# Display.net
KiCad netlist of a schematic drawn in Altium Designer
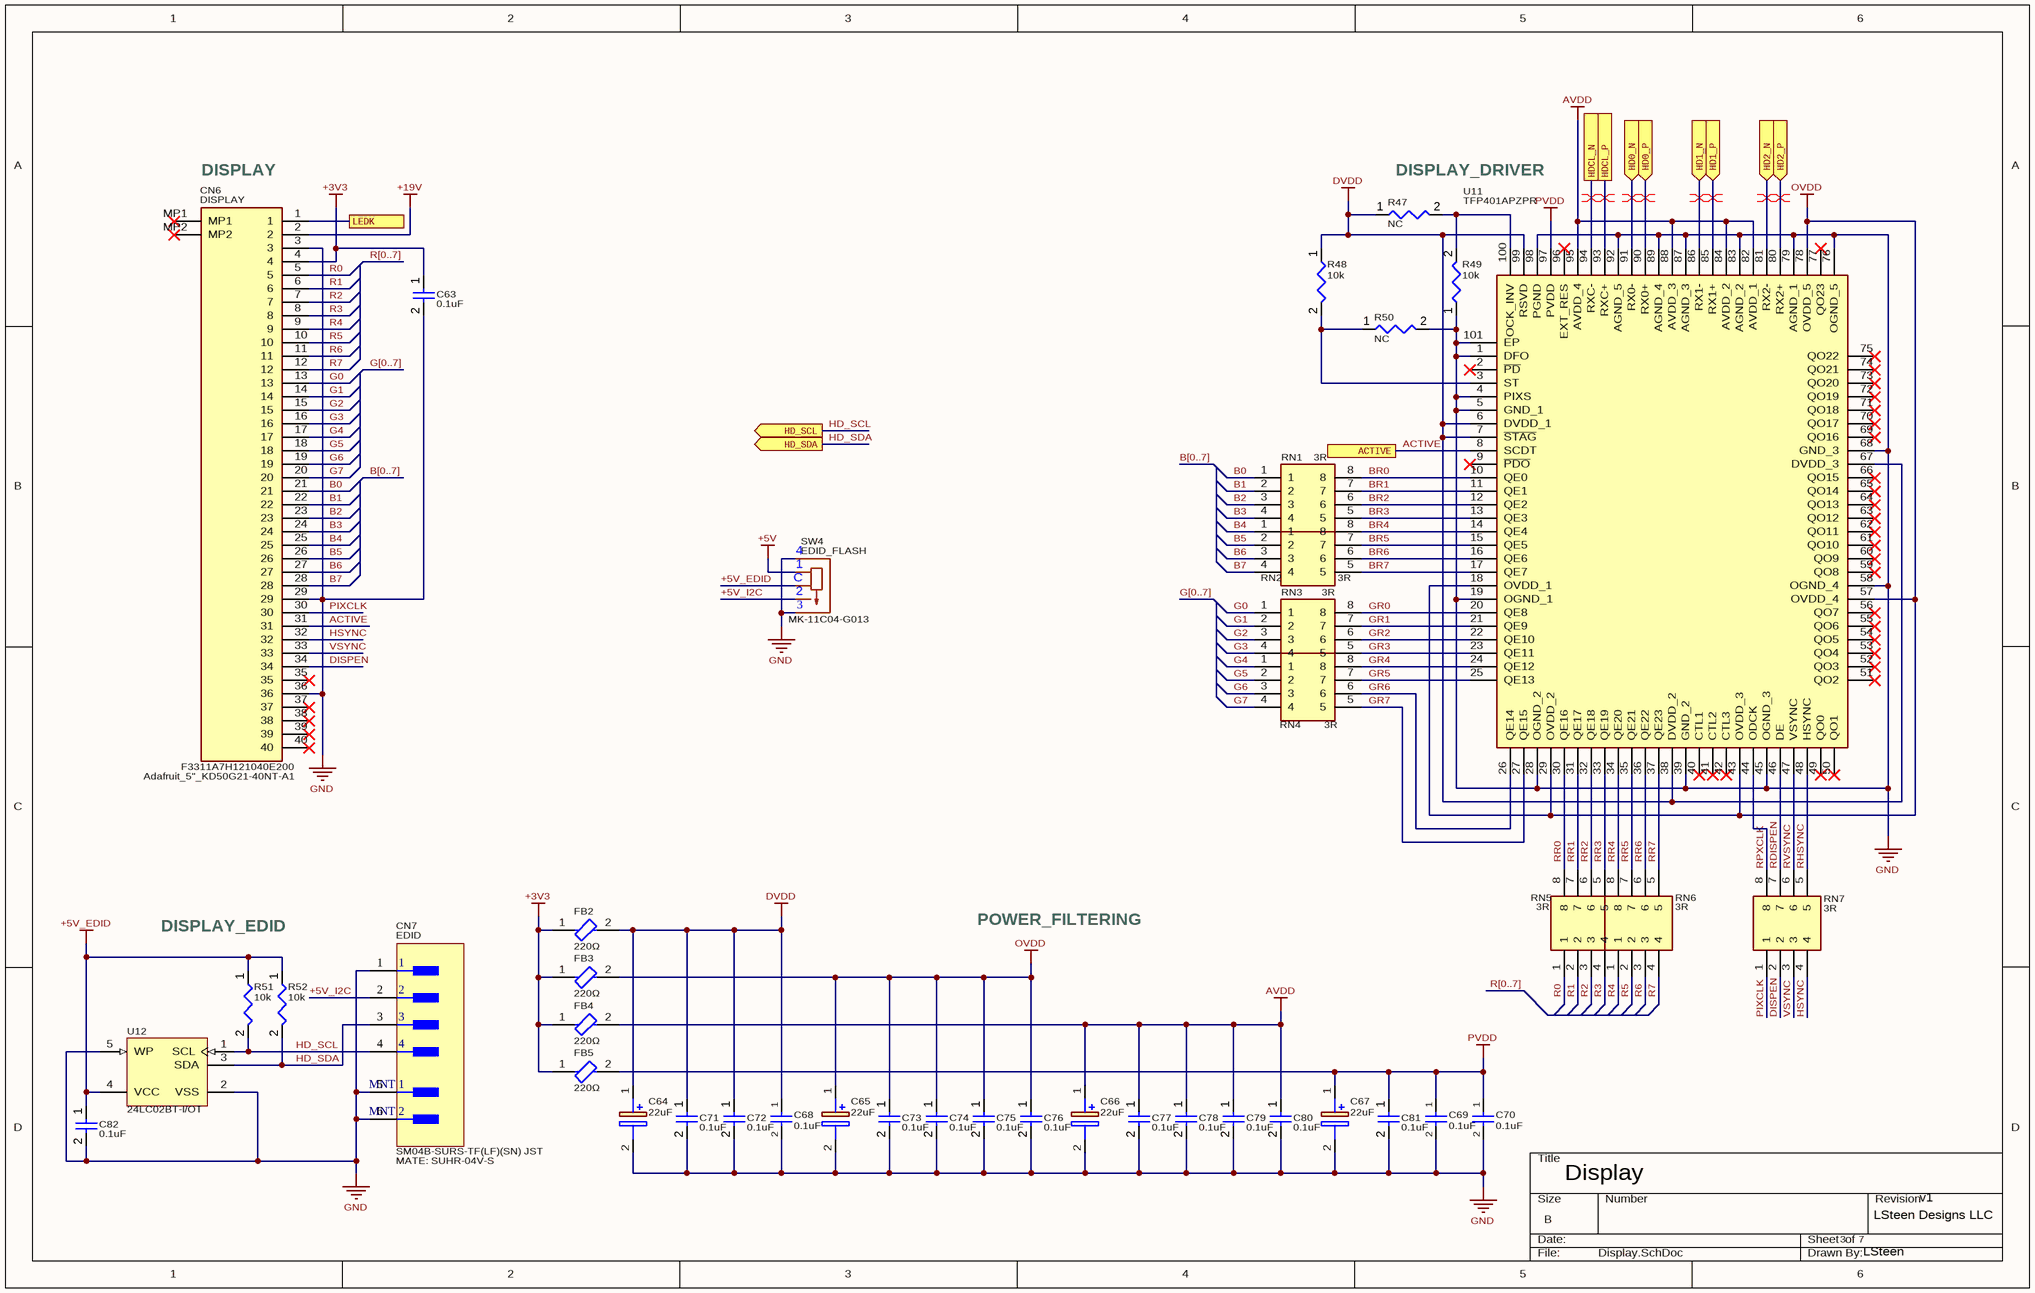
[diagram p0: Display.SchDoc]

(export (version "E")
  (design (tool "Eeschema 10.0.6"))
  (components
    (comp (ref "C63")
      (value "0.1uF")
      (footprint "CAPC1005X56X25LL10T15")
      (description "Chip Capacitor, 0.1 uF, +/- 5%, 16 V, 0402 (1005 Metric)")
      (fields (field (name "TOLERANCE") "5%"))
      (libsource (lib "Colorado Technical University") (part "CAP-NP-2"))
    )
    (comp (ref "C64")
      (value "22uF")
      (footprint "SamacSys:CAPPC2114X150N")
      (description "Capacitor Polarised")
      (fields
        (field (name "MANUFACTURER_PART_NUMBER") "TACR226K006XTA")
        (field (name "MOUSER PART NUMBER") "581-TACR226K006X")
      )
      (libsource (lib "SamacSys") (part "TACR226K006XTA"))
    )
    (comp (ref "C65")
      (value "22uF")
      (footprint "SamacSys:CAPPC2114X150N")
      (description "Capacitor Polarised")
      (fields
        (field (name "MANUFACTURER_PART_NUMBER") "TACR226K006XTA")
        (field (name "MOUSER PART NUMBER") "581-TACR226K006X")
      )
      (libsource (lib "SamacSys") (part "TACR226K006XTA"))
    )
    (comp (ref "C66")
      (value "22uF")
      (footprint "SamacSys:CAPPC2114X150N")
      (description "Capacitor Polarised")
      (fields
        (field (name "MANUFACTURER_PART_NUMBER") "TACR226K006XTA")
        (field (name "MOUSER PART NUMBER") "581-TACR226K006X")
      )
      (libsource (lib "SamacSys") (part "TACR226K006XTA"))
    )
    (comp (ref "C67")
      (value "22uF")
      (footprint "SamacSys:CAPPC2114X150N")
      (description "Capacitor Polarised")
      (fields
        (field (name "MANUFACTURER_PART_NUMBER") "TACR226K006XTA")
        (field (name "MOUSER PART NUMBER") "581-TACR226K006X")
      )
      (libsource (lib "SamacSys") (part "TACR226K006XTA"))
    )
    (comp (ref "C68")
      (value "0.1uF")
      (footprint "SamacSys:CAPC1005X55N")
      (description "C0402")
      (libsource (lib "SamacSys") (part "C0402"))
    )
    (comp (ref "C69")
      (value "0.1uF")
      (footprint "SamacSys:CAPC1005X55N")
      (description "C0402")
      (libsource (lib "SamacSys") (part "C0402"))
    )
    (comp (ref "C70")
      (value "0.1uF")
      (footprint "SamacSys:CAPC1005X55N")
      (description "C0402")
      (libsource (lib "SamacSys") (part "C0402"))
    )
    (comp (ref "C71")
      (value "0.1uF")
      (footprint "CAPC1005X56X25LL10T15")
      (description "Chip Capacitor, 0.1 uF, +/- 5%, 16 V, 0402 (1005 Metric)")
      (fields (field (name "TOLERANCE") "5%"))
      (libsource (lib "Colorado Technical University") (part "CAP-NP-2"))
    )
    (comp (ref "C72")
      (value "0.1uF")
      (footprint "CAPC1005X56X25LL10T15")
      (description "Chip Capacitor, 0.1 uF, +/- 5%, 16 V, 0402 (1005 Metric)")
      (fields (field (name "TOLERANCE") "5%"))
      (libsource (lib "Colorado Technical University") (part "CAP-NP-2"))
    )
    (comp (ref "C73")
      (value "0.1uF")
      (footprint "CAPC1005X56X25LL10T15")
      (description "Chip Capacitor, 0.1 uF, +/- 5%, 16 V, 0402 (1005 Metric)")
      (fields (field (name "TOLERANCE") "5%"))
      (libsource (lib "Colorado Technical University") (part "CAP-NP-2"))
    )
    (comp (ref "C74")
      (value "0.1uF")
      (footprint "CAPC1005X56X25LL10T15")
      (description "Chip Capacitor, 0.1 uF, +/- 5%, 16 V, 0402 (1005 Metric)")
      (fields (field (name "TOLERANCE") "5%"))
      (libsource (lib "Colorado Technical University") (part "CAP-NP-2"))
    )
    (comp (ref "C75")
      (value "0.1uF")
      (footprint "CAPC1005X56X25LL10T15")
      (description "Chip Capacitor, 0.1 uF, +/- 5%, 16 V, 0402 (1005 Metric)")
      (fields (field (name "TOLERANCE") "5%"))
      (libsource (lib "Colorado Technical University") (part "CAP-NP-2"))
    )
    (comp (ref "C76")
      (value "0.1uF")
      (footprint "CAPC1005X56X25LL10T15")
      (description "Chip Capacitor, 0.1 uF, +/- 5%, 16 V, 0402 (1005 Metric)")
      (fields (field (name "TOLERANCE") "5%"))
      (libsource (lib "Colorado Technical University") (part "CAP-NP-2"))
    )
    (comp (ref "C77")
      (value "0.1uF")
      (footprint "CAPC1005X56X25LL10T15")
      (description "Chip Capacitor, 0.1 uF, +/- 5%, 16 V, 0402 (1005 Metric)")
      (fields (field (name "TOLERANCE") "5%"))
      (libsource (lib "Colorado Technical University") (part "CAP-NP-2"))
    )
    (comp (ref "C78")
      (value "0.1uF")
      (footprint "CAPC1005X56X25LL10T15")
      (description "Chip Capacitor, 0.1 uF, +/- 5%, 16 V, 0402 (1005 Metric)")
      (fields (field (name "TOLERANCE") "5%"))
      (libsource (lib "Colorado Technical University") (part "CAP-NP-2"))
    )
    (comp (ref "C79")
      (value "0.1uF")
      (footprint "CAPC1005X56X25LL10T15")
      (description "Chip Capacitor, 0.1 uF, +/- 5%, 16 V, 0402 (1005 Metric)")
      (fields (field (name "TOLERANCE") "5%"))
      (libsource (lib "Colorado Technical University") (part "CAP-NP-2"))
    )
    (comp (ref "C80")
      (value "0.1uF")
      (footprint "CAPC1005X56X25LL10T15")
      (description "Chip Capacitor, 0.1 uF, +/- 5%, 16 V, 0402 (1005 Metric)")
      (fields (field (name "TOLERANCE") "5%"))
      (libsource (lib "Colorado Technical University") (part "CAP-NP-2"))
    )
    (comp (ref "C81")
      (value "0.1uF")
      (footprint "CAPC1005X56X25LL10T15")
      (description "Chip Capacitor, 0.1 uF, +/- 5%, 16 V, 0402 (1005 Metric)")
      (fields (field (name "TOLERANCE") "5%"))
      (libsource (lib "Colorado Technical University") (part "CAP-NP-2"))
    )
    (comp (ref "C82")
      (value "0.1uF")
      (footprint "CAPC1005X56X25LL10T15")
      (description "Chip Capacitor, 0.1 uF, +/- 5%, 16 V, 0402 (1005 Metric)")
      (fields (field (name "TOLERANCE") "5%"))
      (libsource (lib "Colorado Technical University") (part "CAP-NP-2"))
    )
    (comp (ref "CN6")
      (value "DISPLAY")
      (footprint "SamacSys:F3311A7H121040E200")
      (description "Connector")
      (fields (field (name "MANUFACTURER_PART_NUMBER") "F3311A7H121040E200"))
      (libsource (lib "*") (part "F3311A7H121040E200"))
    )
    (comp (ref "CN7")
      (value "EDID")
      (footprint "FP-SM04B-SURS-TF_LF_SN-MFG")
      (description "CONN HEADER SMD R/A 4POS 0.8MM")
      (libsource (lib "Altium Content Vault") (part "3b6f738a5616415d78381ad43816e4a"))
    )
    (comp (ref "FB2")
      (value "220Ω")
      (footprint "FP-BLM18-0_15-t0_5-IPC_B")
      (description "Chip Ferrite Bead, 0603, 220Ω @ 100MHz, 25%, 0.04Ω, 2.5A")
      (libsource (lib "Altium Content Vault") (part "5f30dd21d616792df468990f7003faa"))
    )
    (comp (ref "FB3")
      (value "220Ω")
      (footprint "FP-BLM18-0_15-t0_5-IPC_B")
      (description "Chip Ferrite Bead, 0603, 220Ω @ 100MHz, 25%, 0.04Ω, 2.5A")
      (libsource (lib "Altium Content Vault") (part "5f30dd21d616792df468990f7003faa"))
    )
    (comp (ref "FB4")
      (value "220Ω")
      (footprint "FP-BLM18-0_15-t0_5-IPC_B")
      (description "Chip Ferrite Bead, 0603, 220Ω @ 100MHz, 25%, 0.04Ω, 2.5A")
      (libsource (lib "Altium Content Vault") (part "5f30dd21d616792df468990f7003faa"))
    )
    (comp (ref "FB5")
      (value "220Ω")
      (footprint "FP-BLM18-0_15-t0_5-IPC_B")
      (description "Chip Ferrite Bead, 0603, 220Ω @ 100MHz, 25%, 0.04Ω, 2.5A")
      (libsource (lib "Altium Content Vault") (part "5f30dd21d616792df468990f7003faa"))
    )
    (comp (ref "R47")
      (value "NC")
      (footprint "RESC0402(1005)_L")
      (description "Chip Resistor, 0 Ohms, +/-5 %, 63 mW, -55 to 155 degC, 0402")
      (fields (field (name "TOLERANCE") "5%") (field (name "POWER") "63mW"))
      (libsource (lib "Colorado Technical University") (part "RES-2"))
    )
    (comp (ref "R48")
      (value "10k")
      (footprint "RESC0402(1005)_L")
      (description "Chip Resistor, 10 kOhms, +/-5 %, 63 mW, -55 to 155 degC, 0402")
      (fields (field (name "TOLERANCE") "5%") (field (name "POWER") "63mW"))
      (libsource (lib "Colorado Technical University") (part "RES-2"))
    )
    (comp (ref "R49")
      (value "10k")
      (footprint "RESC0402(1005)_L")
      (description "Chip Resistor, 10 kOhms, +/-5 %, 63 mW, -55 to 155 degC, 0402")
      (fields (field (name "TOLERANCE") "5%") (field (name "POWER") "63mW"))
      (libsource (lib "Colorado Technical University") (part "RES-2"))
    )
    (comp (ref "R50")
      (value "NC")
      (footprint "RESC0402(1005)_L")
      (description "Chip Resistor, 0 Ohms, +/-5 %, 63 mW, -55 to 155 degC, 0402")
      (fields (field (name "TOLERANCE") "5%") (field (name "POWER") "63mW"))
      (libsource (lib "Colorado Technical University") (part "RES-2"))
    )
    (comp (ref "R51")
      (value "10k")
      (footprint "RESC0402(1005)_L")
      (description "Chip Resistor, 10 kOhms, +/-5 %, 63 mW, -55 to 155 degC, 0402")
      (fields (field (name "TOLERANCE") "5%") (field (name "POWER") "63mW"))
      (libsource (lib "Colorado Technical University") (part "RES-2"))
    )
    (comp (ref "R52")
      (value "10k")
      (footprint "RESC0402(1005)_L")
      (description "Chip Resistor, 10 kOhms, +/-5 %, 63 mW, -55 to 155 degC, 0402")
      (fields (field (name "TOLERANCE") "5%") (field (name "POWER") "63mW"))
      (libsource (lib "Colorado Technical University") (part "RES-2"))
    )
    (comp (ref "RN1")
      (value "3R")
      (footprint "SamacSys:YC124JR0733RL")
      (description "Resistor Network")
      (fields
        (field (name "MANUFACTURER_PART_NUMBER") "YC124-JR-0733RL")
        (field (name "MOUSER PART NUMBER") "603-YC124-JR-0733RL")
      )
      (libsource (lib "") (part "YC124-JR-073RL_1"))
    )
    (comp (ref "RN2")
      (value "3R")
      (footprint "SamacSys:YC124JR0733RL")
      (description "Resistor Network")
      (fields
        (field (name "MANUFACTURER_PART_NUMBER") "YC124-JR-0733RL")
        (field (name "MOUSER PART NUMBER") "603-YC124-JR-0733RL")
      )
      (libsource (lib "") (part "YC124-JR-073RL_1"))
    )
    (comp (ref "RN3")
      (value "3R")
      (footprint "SamacSys:YC124JR0733RL")
      (description "Resistor Network")
      (fields
        (field (name "MANUFACTURER_PART_NUMBER") "YC124-JR-0733RL")
        (field (name "MOUSER PART NUMBER") "603-YC124-JR-0733RL")
      )
      (libsource (lib "") (part "YC124-JR-073RL_1"))
    )
    (comp (ref "RN4")
      (value "3R")
      (footprint "SamacSys:YC124JR0733RL")
      (description "Resistor Network")
      (fields
        (field (name "MANUFACTURER_PART_NUMBER") "YC124-JR-0733RL")
        (field (name "MOUSER PART NUMBER") "603-YC124-JR-0733RL")
      )
      (libsource (lib "") (part "YC124-JR-073RL_1"))
    )
    (comp (ref "RN5")
      (value "3R")
      (footprint "SamacSys:YC124JR0733RL")
      (description "Resistor Network")
      (fields
        (field (name "MANUFACTURER_PART_NUMBER") "YC124-JR-0733RL")
        (field (name "MOUSER PART NUMBER") "603-YC124-JR-0733RL")
      )
      (libsource (lib "SamacSys") (part "YC124-JR-073RL"))
    )
    (comp (ref "RN6")
      (value "3R")
      (footprint "SamacSys:YC124JR0733RL")
      (description "Resistor Network")
      (fields
        (field (name "MANUFACTURER_PART_NUMBER") "YC124-JR-0733RL")
        (field (name "MOUSER PART NUMBER") "603-YC124-JR-0733RL")
      )
      (libsource (lib "SamacSys") (part "YC124-JR-073RL"))
    )
    (comp (ref "RN7")
      (value "3R")
      (footprint "SamacSys:YC124JR0733RL")
      (description "Resistor Network")
      (fields
        (field (name "MANUFACTURER_PART_NUMBER") "YC124-JR-0733RL")
        (field (name "MOUSER PART NUMBER") "603-YC124-JR-0733RL")
      )
      (libsource (lib "SamacSys") (part "YC124-JR-073RL"))
    )
    (comp (ref "SW4")
      (value "EDID_FLASH")
      (footprint "SW-SMD_MK-11C04-G013")
      (description "SPDT 1A 6V Slide Switch")
      (libsource (lib "Schlib1") (part "MK-11C04-G013"))
    )
    (comp (ref "U11")
      (value "TFP401APZPR")
      (footprint "SamacSys:QFP50P1600X1600X120-100N")
      (description "Integrated Circuit")
      (fields (field (name "MOUSER PART NUMBER") "595-TFP401APZPR"))
      (libsource (lib "SamacSys") (part "TFP401APZPR"))
    )
    (comp (ref "U12")
      (value "24LC02BT-I/OT")
      (footprint "SOT-23-OT5_L")
      (description "2Kbit, 400kHz, 2.5V, I2C Serial EEPROM, 5-Pin SOT-23, Industrial Temperature, Tape and Reel")
      (libsource (lib "Altium Content Vault") (part "MEM-SEEPROM-24AA16-OT-5"))
    )
  )
  (nets
    (net (code "1") (name "+3V3") (class "Default")
      (node (ref "C63") (pin "1") (pinfunction "1_1") (pintype "passive"))
      (node (ref "CN6") (pin "4") (pinfunction "4_4") (pintype "passive"))
      (node (ref "FB2") (pin "1") (pinfunction "1_1") (pintype "passive"))
      (node (ref "FB3") (pin "1") (pinfunction "1_1") (pintype "passive"))
      (node (ref "FB4") (pin "1") (pinfunction "1_1") (pintype "passive"))
      (node (ref "FB5") (pin "1") (pinfunction "1_1") (pintype "passive"))
    )
    (net (code "2") (name "+5V") (class "Default")
      (node (ref "SW4") (pin "1") (pinfunction "1_1") (pintype "power_in"))
    )
    (net (code "3") (name "+5V_EDID") (class "Default")
      (node (ref "C82") (pin "1") (pinfunction "1_1") (pintype "passive"))
      (node (ref "R51") (pin "1") (pinfunction "1_1") (pintype "passive"))
      (node (ref "R52") (pin "1") (pinfunction "1_1") (pintype "passive"))
      (node (ref "SW4") (pin "C") (pinfunction "C_C") (pintype "power_in"))
      (node (ref "U12") (pin "4") (pinfunction "VCC_4") (pintype "power_in"))
    )
    (net (code "4") (name "+19V") (class "Default")
      (node (ref "CN6") (pin "2") (pinfunction "2_2") (pintype "passive"))
    )
    (net (code "5") (name "/+5V_I2C") (class "Default")
      (node (ref "CN7") (pin "2") (pinfunction "2_2") (pintype "passive"))
      (node (ref "SW4") (pin "2") (pinfunction "2_2") (pintype "passive"))
    )
    (net (code "6") (name "/ACTIVE") (class "Default")
      (node (ref "CN6") (pin "31") (pinfunction "31_31") (pintype "passive"))
      (node (ref "U11") (pin "8") (pinfunction "SCDT_8") (pintype "passive"))
    )
    (net (code "7") (name "/B0") (class "Default")
      (node (ref "CN6") (pin "21") (pinfunction "21_21") (pintype "passive"))
      (node (ref "RN1") (pin "1") (pinfunction "1_1") (pintype "passive"))
    )
    (net (code "8") (name "/B1") (class "Default")
      (node (ref "CN6") (pin "22") (pinfunction "22_22") (pintype "passive"))
      (node (ref "RN1") (pin "2") (pinfunction "2_2") (pintype "passive"))
    )
    (net (code "9") (name "/B2") (class "Default")
      (node (ref "CN6") (pin "23") (pinfunction "23_23") (pintype "passive"))
      (node (ref "RN1") (pin "3") (pinfunction "3_3") (pintype "passive"))
    )
    (net (code "10") (name "/B3") (class "Default")
      (node (ref "CN6") (pin "24") (pinfunction "24_24") (pintype "passive"))
      (node (ref "RN1") (pin "4") (pinfunction "4_4") (pintype "passive"))
    )
    (net (code "11") (name "/B4") (class "Default")
      (node (ref "CN6") (pin "25") (pinfunction "25_25") (pintype "passive"))
      (node (ref "RN2") (pin "1") (pinfunction "1_1") (pintype "passive"))
    )
    (net (code "12") (name "/B5") (class "Default")
      (node (ref "CN6") (pin "26") (pinfunction "26_26") (pintype "passive"))
      (node (ref "RN2") (pin "2") (pinfunction "2_2") (pintype "passive"))
    )
    (net (code "13") (name "/B6") (class "Default")
      (node (ref "CN6") (pin "27") (pinfunction "27_27") (pintype "passive"))
      (node (ref "RN2") (pin "3") (pinfunction "3_3") (pintype "passive"))
    )
    (net (code "14") (name "/B7") (class "Default")
      (node (ref "CN6") (pin "28") (pinfunction "28_28") (pintype "passive"))
      (node (ref "RN2") (pin "4") (pinfunction "4_4") (pintype "passive"))
    )
    (net (code "15") (name "/BR0") (class "Default")
      (node (ref "RN1") (pin "8") (pinfunction "8_8") (pintype "passive"))
      (node (ref "U11") (pin "10") (pinfunction "QE0_10") (pintype "passive"))
    )
    (net (code "16") (name "/BR1") (class "Default")
      (node (ref "RN1") (pin "7") (pinfunction "7_7") (pintype "passive"))
      (node (ref "U11") (pin "11") (pinfunction "QE1_11") (pintype "passive"))
    )
    (net (code "17") (name "/BR2") (class "Default")
      (node (ref "RN1") (pin "6") (pinfunction "6_6") (pintype "passive"))
      (node (ref "U11") (pin "12") (pinfunction "QE2_12") (pintype "passive"))
    )
    (net (code "18") (name "/BR3") (class "Default")
      (node (ref "RN1") (pin "5") (pinfunction "5_5") (pintype "passive"))
      (node (ref "U11") (pin "13") (pinfunction "QE3_13") (pintype "passive"))
    )
    (net (code "19") (name "/BR4") (class "Default")
      (node (ref "RN2") (pin "8") (pinfunction "8_8") (pintype "passive"))
      (node (ref "U11") (pin "14") (pinfunction "QE4_14") (pintype "passive"))
    )
    (net (code "20") (name "/BR5") (class "Default")
      (node (ref "RN2") (pin "7") (pinfunction "7_7") (pintype "passive"))
      (node (ref "U11") (pin "15") (pinfunction "QE5_15") (pintype "passive"))
    )
    (net (code "21") (name "/BR6") (class "Default")
      (node (ref "RN2") (pin "6") (pinfunction "6_6") (pintype "passive"))
      (node (ref "U11") (pin "16") (pinfunction "QE6_16") (pintype "passive"))
    )
    (net (code "22") (name "/BR7") (class "Default")
      (node (ref "RN2") (pin "5") (pinfunction "5_5") (pintype "passive"))
      (node (ref "U11") (pin "17") (pinfunction "QE7_17") (pintype "passive"))
    )
    (net (code "24") (name "/DISPEN") (class "Default")
      (node (ref "CN6") (pin "34") (pinfunction "34_34") (pintype "passive"))
      (node (ref "RN7") (pin "2") (pinfunction "2_2") (pintype "passive"))
    )
    (net (code "25") (name "/G0") (class "Default")
      (node (ref "CN6") (pin "13") (pinfunction "13_13") (pintype "passive"))
      (node (ref "RN3") (pin "1") (pinfunction "1_1") (pintype "passive"))
    )
    (net (code "26") (name "/G1") (class "Default")
      (node (ref "CN6") (pin "14") (pinfunction "14_14") (pintype "passive"))
      (node (ref "RN3") (pin "2") (pinfunction "2_2") (pintype "passive"))
    )
    (net (code "27") (name "/G2") (class "Default")
      (node (ref "CN6") (pin "15") (pinfunction "15_15") (pintype "passive"))
      (node (ref "RN3") (pin "3") (pinfunction "3_3") (pintype "passive"))
    )
    (net (code "28") (name "/G3") (class "Default")
      (node (ref "CN6") (pin "16") (pinfunction "16_16") (pintype "passive"))
      (node (ref "RN3") (pin "4") (pinfunction "4_4") (pintype "passive"))
    )
    (net (code "29") (name "/G4") (class "Default")
      (node (ref "CN6") (pin "17") (pinfunction "17_17") (pintype "passive"))
      (node (ref "RN4") (pin "1") (pinfunction "1_1") (pintype "passive"))
    )
    (net (code "30") (name "/G5") (class "Default")
      (node (ref "CN6") (pin "18") (pinfunction "18_18") (pintype "passive"))
      (node (ref "RN4") (pin "2") (pinfunction "2_2") (pintype "passive"))
    )
    (net (code "31") (name "/G6") (class "Default")
      (node (ref "CN6") (pin "19") (pinfunction "19_19") (pintype "passive"))
      (node (ref "RN4") (pin "3") (pinfunction "3_3") (pintype "passive"))
    )
    (net (code "32") (name "/G7") (class "Default")
      (node (ref "CN6") (pin "20") (pinfunction "20_20") (pintype "passive"))
      (node (ref "RN4") (pin "4") (pinfunction "4_4") (pintype "passive"))
    )
    (net (code "33") (name "/GR0") (class "Default")
      (node (ref "RN3") (pin "8") (pinfunction "8_8") (pintype "passive"))
      (node (ref "U11") (pin "20") (pinfunction "QE8_20") (pintype "passive"))
    )
    (net (code "34") (name "/GR1") (class "Default")
      (node (ref "RN3") (pin "7") (pinfunction "7_7") (pintype "passive"))
      (node (ref "U11") (pin "21") (pinfunction "QE9_21") (pintype "passive"))
    )
    (net (code "35") (name "/GR2") (class "Default")
      (node (ref "RN3") (pin "6") (pinfunction "6_6") (pintype "passive"))
      (node (ref "U11") (pin "22") (pinfunction "QE10_22") (pintype "passive"))
    )
    (net (code "36") (name "/GR3") (class "Default")
      (node (ref "RN3") (pin "5") (pinfunction "5_5") (pintype "passive"))
      (node (ref "U11") (pin "23") (pinfunction "QE11_23") (pintype "passive"))
    )
    (net (code "37") (name "/GR4") (class "Default")
      (node (ref "RN4") (pin "8") (pinfunction "8_8") (pintype "passive"))
      (node (ref "U11") (pin "24") (pinfunction "QE12_24") (pintype "passive"))
    )
    (net (code "38") (name "/GR5") (class "Default")
      (node (ref "RN4") (pin "7") (pinfunction "7_7") (pintype "passive"))
      (node (ref "U11") (pin "25") (pinfunction "QE13_25") (pintype "passive"))
    )
    (net (code "39") (name "/GR6") (class "Default")
      (node (ref "RN4") (pin "6") (pinfunction "6_6") (pintype "passive"))
      (node (ref "U11") (pin "26") (pinfunction "QE14_26") (pintype "passive"))
    )
    (net (code "40") (name "/GR7") (class "Default")
      (node (ref "RN4") (pin "5") (pinfunction "5_5") (pintype "passive"))
      (node (ref "U11") (pin "27") (pinfunction "QE15_27") (pintype "passive"))
    )
    (net (code "42") (name "/HD0_N") (class "Default")
      (node (ref "U11") (pin "91") (pinfunction "RX0-_91") (pintype "passive"))
    )
    (net (code "43") (name "/HD0_P") (class "Default")
      (node (ref "U11") (pin "90") (pinfunction "RX0+_90") (pintype "passive"))
    )
    (net (code "44") (name "/HD1_N") (class "Default")
      (node (ref "U11") (pin "86") (pinfunction "RX1-_86") (pintype "passive"))
    )
    (net (code "45") (name "/HD1_P") (class "Default")
      (node (ref "U11") (pin "85") (pinfunction "RX1+_85") (pintype "passive"))
    )
    (net (code "46") (name "/HD2_N") (class "Default")
      (node (ref "U11") (pin "81") (pinfunction "RX2-_81") (pintype "passive"))
    )
    (net (code "47") (name "/HD2_P") (class "Default")
      (node (ref "U11") (pin "80") (pinfunction "RX2+_80") (pintype "passive"))
    )
    (net (code "48") (name "/HDCL_N") (class "Default")
      (node (ref "U11") (pin "94") (pinfunction "RXC-_94") (pintype "passive"))
    )
    (net (code "49") (name "/HDCL_P") (class "Default")
      (node (ref "U11") (pin "93") (pinfunction "RXC+_93") (pintype "passive"))
    )
    (net (code "50") (name "/HD_SCL") (class "Default")
      (node (ref "CN7") (pin "4") (pinfunction "4_4") (pintype "passive"))
      (node (ref "R51") (pin "2") (pinfunction "2_2") (pintype "passive"))
      (node (ref "U12") (pin "1") (pinfunction "SCL_1") (pintype "input"))
    )
    (net (code "51") (name "/HD_SDA") (class "Default")
      (node (ref "CN7") (pin "3") (pinfunction "3_3") (pintype "passive"))
      (node (ref "R52") (pin "2") (pinfunction "2_2") (pintype "passive"))
      (node (ref "U12") (pin "3") (pinfunction "SDA_3") (pintype "passive"))
    )
    (net (code "52") (name "/HSYNC") (class "Default")
      (node (ref "CN6") (pin "32") (pinfunction "32_32") (pintype "passive"))
      (node (ref "RN7") (pin "4") (pinfunction "4_4") (pintype "passive"))
    )
    (net (code "53") (name "/LEDK") (class "Default")
      (node (ref "CN6") (pin "1") (pinfunction "1_1") (pintype "passive"))
    )
    (net (code "54") (name "/PIXCLK") (class "Default")
      (node (ref "CN6") (pin "30") (pinfunction "30_30") (pintype "passive"))
      (node (ref "RN7") (pin "1") (pinfunction "1_1") (pintype "passive"))
    )
    (net (code "55") (name "/R0") (class "Default")
      (node (ref "CN6") (pin "5") (pinfunction "5_5") (pintype "passive"))
      (node (ref "RN5") (pin "1") (pinfunction "1_1") (pintype "passive"))
    )
    (net (code "56") (name "/R1") (class "Default")
      (node (ref "CN6") (pin "6") (pinfunction "6_6") (pintype "passive"))
      (node (ref "RN5") (pin "2") (pinfunction "2_2") (pintype "passive"))
    )
    (net (code "57") (name "/R2") (class "Default")
      (node (ref "CN6") (pin "7") (pinfunction "7_7") (pintype "passive"))
      (node (ref "RN5") (pin "3") (pinfunction "3_3") (pintype "passive"))
    )
    (net (code "58") (name "/R3") (class "Default")
      (node (ref "CN6") (pin "8") (pinfunction "8_8") (pintype "passive"))
      (node (ref "RN5") (pin "4") (pinfunction "4_4") (pintype "passive"))
    )
    (net (code "59") (name "/R4") (class "Default")
      (node (ref "CN6") (pin "9") (pinfunction "9_9") (pintype "passive"))
      (node (ref "RN6") (pin "1") (pinfunction "1_1") (pintype "passive"))
    )
    (net (code "60") (name "/R5") (class "Default")
      (node (ref "CN6") (pin "10") (pinfunction "10_10") (pintype "passive"))
      (node (ref "RN6") (pin "2") (pinfunction "2_2") (pintype "passive"))
    )
    (net (code "61") (name "/R6") (class "Default")
      (node (ref "CN6") (pin "11") (pinfunction "11_11") (pintype "passive"))
      (node (ref "RN6") (pin "3") (pinfunction "3_3") (pintype "passive"))
    )
    (net (code "62") (name "/R7") (class "Default")
      (node (ref "CN6") (pin "12") (pinfunction "12_12") (pintype "passive"))
      (node (ref "RN6") (pin "4") (pinfunction "4_4") (pintype "passive"))
    )
    (net (code "63") (name "/RDISPEN") (class "Default")
      (node (ref "RN7") (pin "7") (pinfunction "7_7") (pintype "passive"))
      (node (ref "U11") (pin "46") (pinfunction "DE_46") (pintype "passive"))
    )
    (net (code "64") (name "/RHSYNC") (class "Default")
      (node (ref "RN7") (pin "5") (pinfunction "5_5") (pintype "passive"))
      (node (ref "U11") (pin "48") (pinfunction "HSYNC_48") (pintype "passive"))
    )
    (net (code "65") (name "/RPXCLK") (class "Default")
      (node (ref "RN7") (pin "8") (pinfunction "8_8") (pintype "passive"))
      (node (ref "U11") (pin "44") (pinfunction "ODCK_44") (pintype "passive"))
    )
    (net (code "66") (name "/RR0") (class "Default")
      (node (ref "RN5") (pin "8") (pinfunction "8_8") (pintype "passive"))
      (node (ref "U11") (pin "30") (pinfunction "QE16_30") (pintype "passive"))
    )
    (net (code "67") (name "/RR1") (class "Default")
      (node (ref "RN5") (pin "7") (pinfunction "7_7") (pintype "passive"))
      (node (ref "U11") (pin "31") (pinfunction "QE17_31") (pintype "passive"))
    )
    (net (code "68") (name "/RR2") (class "Default")
      (node (ref "RN5") (pin "6") (pinfunction "6_6") (pintype "passive"))
      (node (ref "U11") (pin "32") (pinfunction "QE18_32") (pintype "passive"))
    )
    (net (code "69") (name "/RR3") (class "Default")
      (node (ref "RN5") (pin "5") (pinfunction "5_5") (pintype "passive"))
      (node (ref "U11") (pin "33") (pinfunction "QE19_33") (pintype "passive"))
    )
    (net (code "70") (name "/RR4") (class "Default")
      (node (ref "RN6") (pin "8") (pinfunction "8_8") (pintype "passive"))
      (node (ref "U11") (pin "34") (pinfunction "QE20_34") (pintype "passive"))
    )
    (net (code "71") (name "/RR5") (class "Default")
      (node (ref "RN6") (pin "7") (pinfunction "7_7") (pintype "passive"))
      (node (ref "U11") (pin "35") (pinfunction "QE21_35") (pintype "passive"))
    )
    (net (code "72") (name "/RR6") (class "Default")
      (node (ref "RN6") (pin "6") (pinfunction "6_6") (pintype "passive"))
      (node (ref "U11") (pin "36") (pinfunction "QE22_36") (pintype "passive"))
    )
    (net (code "73") (name "/RR7") (class "Default")
      (node (ref "RN6") (pin "5") (pinfunction "5_5") (pintype "passive"))
      (node (ref "U11") (pin "37") (pinfunction "QE23_37") (pintype "passive"))
    )
    (net (code "74") (name "/RVSYNC") (class "Default")
      (node (ref "RN7") (pin "6") (pinfunction "6_6") (pintype "passive"))
      (node (ref "U11") (pin "47") (pinfunction "VSYNC_47") (pintype "passive"))
    )
    (net (code "76") (name "/VSYNC") (class "Default")
      (node (ref "CN6") (pin "33") (pinfunction "33_33") (pintype "passive"))
      (node (ref "RN7") (pin "3") (pinfunction "3_3") (pintype "passive"))
    )
    (net (code "77") (name "AVDD") (class "Default")
      (node (ref "C66") (pin "1") (pinfunction "+_1") (pintype "passive"))
      (node (ref "C77") (pin "1") (pinfunction "1_1") (pintype "passive"))
      (node (ref "C78") (pin "1") (pinfunction "1_1") (pintype "passive"))
      (node (ref "C79") (pin "1") (pinfunction "1_1") (pintype "passive"))
      (node (ref "C80") (pin "1") (pinfunction "1_1") (pintype "passive"))
      (node (ref "FB4") (pin "2") (pinfunction "2_2") (pintype "passive"))
      (node (ref "U11") (pin "82") (pinfunction "AVDD_1_82") (pintype "passive"))
      (node (ref "U11") (pin "84") (pinfunction "AVDD_2_84") (pintype "passive"))
      (node (ref "U11") (pin "88") (pinfunction "AVDD_3_88") (pintype "passive"))
      (node (ref "U11") (pin "95") (pinfunction "AVDD_4_95") (pintype "passive"))
    )
    (net (code "78") (name "DVDD") (class "Default")
      (node (ref "C64") (pin "1") (pinfunction "+_1") (pintype "passive"))
      (node (ref "C68") (pin "1") (pinfunction "1_1") (pintype "passive"))
      (node (ref "C71") (pin "1") (pinfunction "1_1") (pintype "passive"))
      (node (ref "C72") (pin "1") (pinfunction "1_1") (pintype "passive"))
      (node (ref "FB2") (pin "2") (pinfunction "2_2") (pintype "passive"))
      (node (ref "R47") (pin "1") (pinfunction "1_1") (pintype "passive"))
      (node (ref "R48") (pin "1") (pinfunction "1_1") (pintype "passive"))
      (node (ref "U11") (pin "38") (pinfunction "DVDD_2_38") (pintype "passive"))
      (node (ref "U11") (pin "6") (pinfunction "DVDD_1_6") (pintype "passive"))
      (node (ref "U11") (pin "67") (pinfunction "DVDD_3_67") (pintype "passive"))
      (node (ref "U11") (pin "7") (pinfunction "~{STAG}_7") (pintype "passive"))
      (node (ref "U11") (pin "99") (pinfunction "RSVD_99") (pintype "passive"))
    )
    (net (code "79") (name "GND") (class "Default")
      (node (ref "C63") (pin "2") (pinfunction "2_2") (pintype "passive"))
      (node (ref "C64") (pin "2") (pinfunction "-_2") (pintype "passive"))
      (node (ref "C65") (pin "2") (pinfunction "-_2") (pintype "passive"))
      (node (ref "C66") (pin "2") (pinfunction "-_2") (pintype "passive"))
      (node (ref "C67") (pin "2") (pinfunction "-_2") (pintype "passive"))
      (node (ref "C68") (pin "2") (pinfunction "2_2") (pintype "passive"))
      (node (ref "C69") (pin "2") (pinfunction "2_2") (pintype "passive"))
      (node (ref "C70") (pin "2") (pinfunction "2_2") (pintype "passive"))
      (node (ref "C71") (pin "2") (pinfunction "2_2") (pintype "passive"))
      (node (ref "C72") (pin "2") (pinfunction "2_2") (pintype "passive"))
      (node (ref "C73") (pin "2") (pinfunction "2_2") (pintype "passive"))
      (node (ref "C74") (pin "2") (pinfunction "2_2") (pintype "passive"))
      (node (ref "C75") (pin "2") (pinfunction "2_2") (pintype "passive"))
      (node (ref "C76") (pin "2") (pinfunction "2_2") (pintype "passive"))
      (node (ref "C77") (pin "2") (pinfunction "2_2") (pintype "passive"))
      (node (ref "C78") (pin "2") (pinfunction "2_2") (pintype "passive"))
      (node (ref "C79") (pin "2") (pinfunction "2_2") (pintype "passive"))
      (node (ref "C80") (pin "2") (pinfunction "2_2") (pintype "passive"))
      (node (ref "C81") (pin "2") (pinfunction "2_2") (pintype "passive"))
      (node (ref "C82") (pin "2") (pinfunction "2_2") (pintype "passive"))
      (node (ref "CN6") (pin "29") (pinfunction "29_29") (pintype "passive"))
      (node (ref "CN6") (pin "3") (pinfunction "3_3") (pintype "passive"))
      (node (ref "CN6") (pin "36") (pinfunction "36_36") (pintype "passive"))
      (node (ref "CN7") (pin "1") (pinfunction "1_1") (pintype "passive"))
      (node (ref "CN7") (pin "5") (pinfunction "MNT_1_5") (pintype "passive"))
      (node (ref "CN7") (pin "6") (pinfunction "MNT_2_6") (pintype "passive"))
      (node (ref "R49") (pin "1") (pinfunction "1_1") (pintype "passive"))
      (node (ref "R50") (pin "2") (pinfunction "2_2") (pintype "passive"))
      (node (ref "SW4") (pin "3") (pinfunction "NC_3") (pintype "power_in"))
      (node (ref "SW4") (pin "4") (pinfunction "4_4") (pintype "power_in"))
      (node (ref "U11") (pin "1") (pinfunction "DFO_1") (pintype "passive"))
      (node (ref "U11") (pin "101") (pinfunction "EP_101") (pintype "passive"))
      (node (ref "U11") (pin "19") (pinfunction "OGND_1_19") (pintype "passive"))
      (node (ref "U11") (pin "28") (pinfunction "OGND_2_28") (pintype "passive"))
      (node (ref "U11") (pin "39") (pinfunction "GND_2_39") (pintype "passive"))
      (node (ref "U11") (pin "4") (pinfunction "PIXS_4") (pintype "passive"))
      (node (ref "U11") (pin "45") (pinfunction "OGND_3_45") (pintype "passive"))
      (node (ref "U11") (pin "5") (pinfunction "GND_1_5") (pintype "passive"))
      (node (ref "U11") (pin "58") (pinfunction "OGND_4_58") (pintype "passive"))
      (node (ref "U11") (pin "68") (pinfunction "GND_3_68") (pintype "passive"))
      (node (ref "U11") (pin "76") (pinfunction "OGND_5_76") (pintype "passive"))
      (node (ref "U11") (pin "79") (pinfunction "AGND_1_79") (pintype "passive"))
      (node (ref "U11") (pin "83") (pinfunction "AGND_2_83") (pintype "passive"))
      (node (ref "U11") (pin "87") (pinfunction "AGND_3_87") (pintype "passive"))
      (node (ref "U11") (pin "89") (pinfunction "AGND_4_89") (pintype "passive"))
      (node (ref "U11") (pin "92") (pinfunction "AGND_5_92") (pintype "passive"))
      (node (ref "U11") (pin "98") (pinfunction "PGND_98") (pintype "passive"))
      (node (ref "U12") (pin "2") (pinfunction "VSS_2") (pintype "power_in"))
      (node (ref "U12") (pin "5") (pinfunction "WP_5") (pintype "input"))
    )
    (net (code "80") (name "Net-(U11-OCK_INV)") (class "Default")
      (node (ref "R47") (pin "2") (pinfunction "2_2") (pintype "passive"))
      (node (ref "R49") (pin "2") (pinfunction "2_2") (pintype "passive"))
      (node (ref "U11") (pin "100") (pinfunction "OCK_INV_100") (pintype "passive"))
    )
    (net (code "81") (name "Net-(U11-ST)") (class "Default")
      (node (ref "R48") (pin "2") (pinfunction "2_2") (pintype "passive"))
      (node (ref "R50") (pin "1") (pinfunction "1_1") (pintype "passive"))
      (node (ref "U11") (pin "3") (pinfunction "ST_3") (pintype "passive"))
    )
    (net (code "82") (name "OVDD") (class "Default")
      (node (ref "C65") (pin "1") (pinfunction "+_1") (pintype "passive"))
      (node (ref "C73") (pin "1") (pinfunction "1_1") (pintype "passive"))
      (node (ref "C74") (pin "1") (pinfunction "1_1") (pintype "passive"))
      (node (ref "C75") (pin "1") (pinfunction "1_1") (pintype "passive"))
      (node (ref "C76") (pin "1") (pinfunction "1_1") (pintype "passive"))
      (node (ref "FB3") (pin "2") (pinfunction "2_2") (pintype "passive"))
      (node (ref "U11") (pin "18") (pinfunction "OVDD_1_18") (pintype "passive"))
      (node (ref "U11") (pin "29") (pinfunction "OVDD_2_29") (pintype "passive"))
      (node (ref "U11") (pin "43") (pinfunction "OVDD_3_43") (pintype "passive"))
      (node (ref "U11") (pin "57") (pinfunction "OVDD_4_57") (pintype "passive"))
      (node (ref "U11") (pin "78") (pinfunction "OVDD_5_78") (pintype "passive"))
    )
    (net (code "83") (name "PVDD") (class "Default")
      (node (ref "C67") (pin "1") (pinfunction "+_1") (pintype "passive"))
      (node (ref "C69") (pin "1") (pinfunction "1_1") (pintype "passive"))
      (node (ref "C70") (pin "1") (pinfunction "1_1") (pintype "passive"))
      (node (ref "C81") (pin "1") (pinfunction "1_1") (pintype "passive"))
      (node (ref "FB5") (pin "2") (pinfunction "2_2") (pintype "passive"))
      (node (ref "U11") (pin "97") (pinfunction "PVDD_97") (pintype "passive"))
    )
    (net (code "84") (name "unconnected-(CN6-Pad35)") (class "Default")
      (node (ref "CN6") (pin "35") (pinfunction "35_35") (pintype "passive+no_connect"))
    )
    (net (code "85") (name "unconnected-(CN6-Pad37)") (class "Default")
      (node (ref "CN6") (pin "37") (pinfunction "37_37") (pintype "passive+no_connect"))
    )
    (net (code "86") (name "unconnected-(CN6-Pad38)") (class "Default")
      (node (ref "CN6") (pin "38") (pinfunction "38_38") (pintype "passive+no_connect"))
    )
    (net (code "87") (name "unconnected-(CN6-Pad39)") (class "Default")
      (node (ref "CN6") (pin "39") (pinfunction "39_39") (pintype "passive+no_connect"))
    )
    (net (code "88") (name "unconnected-(CN6-Pad40)") (class "Default")
      (node (ref "CN6") (pin "40") (pinfunction "40_40") (pintype "passive+no_connect"))
    )
    (net (code "89") (name "unconnected-(CN6-PadMP1)") (class "Default")
      (node (ref "CN6") (pin "MP1") (pinfunction "MP1_MP1") (pintype "passive+no_connect"))
    )
    (net (code "90") (name "unconnected-(CN6-PadMP2)") (class "Default")
      (node (ref "CN6") (pin "MP2") (pinfunction "MP2_MP2") (pintype "passive+no_connect"))
    )
    (net (code "91") (name "unconnected-(U11-CTL1-Pad40)") (class "Default")
      (node (ref "U11") (pin "40") (pinfunction "CTL1_40") (pintype "passive+no_connect"))
    )
    (net (code "92") (name "unconnected-(U11-CTL2-Pad41)") (class "Default")
      (node (ref "U11") (pin "41") (pinfunction "CTL2_41") (pintype "passive+no_connect"))
    )
    (net (code "93") (name "unconnected-(U11-CTL3-Pad42)") (class "Default")
      (node (ref "U11") (pin "42") (pinfunction "CTL3_42") (pintype "passive+no_connect"))
    )
    (net (code "94") (name "unconnected-(U11-EXT_RES-Pad96)") (class "Default")
      (node (ref "U11") (pin "96") (pinfunction "EXT_RES_96") (pintype "passive+no_connect"))
    )
    (net (code "95") (name "unconnected-(U11-QO0-Pad49)") (class "Default")
      (node (ref "U11") (pin "49") (pinfunction "QO0_49") (pintype "passive+no_connect"))
    )
    (net (code "96") (name "unconnected-(U11-QO1-Pad50)") (class "Default")
      (node (ref "U11") (pin "50") (pinfunction "QO1_50") (pintype "passive+no_connect"))
    )
    (net (code "97") (name "unconnected-(U11-QO2-Pad51)") (class "Default")
      (node (ref "U11") (pin "51") (pinfunction "QO2_51") (pintype "passive+no_connect"))
    )
    (net (code "98") (name "unconnected-(U11-QO3-Pad52)") (class "Default")
      (node (ref "U11") (pin "52") (pinfunction "QO3_52") (pintype "passive+no_connect"))
    )
    (net (code "99") (name "unconnected-(U11-QO4-Pad53)") (class "Default")
      (node (ref "U11") (pin "53") (pinfunction "QO4_53") (pintype "passive+no_connect"))
    )
    (net (code "100") (name "unconnected-(U11-QO5-Pad54)") (class "Default")
      (node (ref "U11") (pin "54") (pinfunction "QO5_54") (pintype "passive+no_connect"))
    )
    (net (code "101") (name "unconnected-(U11-QO6-Pad55)") (class "Default")
      (node (ref "U11") (pin "55") (pinfunction "QO6_55") (pintype "passive+no_connect"))
    )
    (net (code "102") (name "unconnected-(U11-QO7-Pad56)") (class "Default")
      (node (ref "U11") (pin "56") (pinfunction "QO7_56") (pintype "passive+no_connect"))
    )
    (net (code "103") (name "unconnected-(U11-QO8-Pad59)") (class "Default")
      (node (ref "U11") (pin "59") (pinfunction "QO8_59") (pintype "passive+no_connect"))
    )
    (net (code "104") (name "unconnected-(U11-QO9-Pad60)") (class "Default")
      (node (ref "U11") (pin "60") (pinfunction "QO9_60") (pintype "passive+no_connect"))
    )
    (net (code "105") (name "unconnected-(U11-QO10-Pad61)") (class "Default")
      (node (ref "U11") (pin "61") (pinfunction "QO10_61") (pintype "passive+no_connect"))
    )
    (net (code "106") (name "unconnected-(U11-QO11-Pad62)") (class "Default")
      (node (ref "U11") (pin "62") (pinfunction "QO11_62") (pintype "passive+no_connect"))
    )
    (net (code "107") (name "unconnected-(U11-QO12-Pad63)") (class "Default")
      (node (ref "U11") (pin "63") (pinfunction "QO12_63") (pintype "passive+no_connect"))
    )
    (net (code "108") (name "unconnected-(U11-QO13-Pad64)") (class "Default")
      (node (ref "U11") (pin "64") (pinfunction "QO13_64") (pintype "passive+no_connect"))
    )
    (net (code "109") (name "unconnected-(U11-QO14-Pad65)") (class "Default")
      (node (ref "U11") (pin "65") (pinfunction "QO14_65") (pintype "passive+no_connect"))
    )
    (net (code "110") (name "unconnected-(U11-QO15-Pad66)") (class "Default")
      (node (ref "U11") (pin "66") (pinfunction "QO15_66") (pintype "passive+no_connect"))
    )
    (net (code "111") (name "unconnected-(U11-QO16-Pad69)") (class "Default")
      (node (ref "U11") (pin "69") (pinfunction "QO16_69") (pintype "passive+no_connect"))
    )
    (net (code "112") (name "unconnected-(U11-QO17-Pad70)") (class "Default")
      (node (ref "U11") (pin "70") (pinfunction "QO17_70") (pintype "passive+no_connect"))
    )
    (net (code "113") (name "unconnected-(U11-QO18-Pad71)") (class "Default")
      (node (ref "U11") (pin "71") (pinfunction "QO18_71") (pintype "passive+no_connect"))
    )
    (net (code "114") (name "unconnected-(U11-QO19-Pad72)") (class "Default")
      (node (ref "U11") (pin "72") (pinfunction "QO19_72") (pintype "passive+no_connect"))
    )
    (net (code "115") (name "unconnected-(U11-QO20-Pad73)") (class "Default")
      (node (ref "U11") (pin "73") (pinfunction "QO20_73") (pintype "passive+no_connect"))
    )
    (net (code "116") (name "unconnected-(U11-QO21-Pad74)") (class "Default")
      (node (ref "U11") (pin "74") (pinfunction "QO21_74") (pintype "passive+no_connect"))
    )
    (net (code "117") (name "unconnected-(U11-QO22-Pad75)") (class "Default")
      (node (ref "U11") (pin "75") (pinfunction "QO22_75") (pintype "passive+no_connect"))
    )
    (net (code "118") (name "unconnected-(U11-QO23-Pad77)") (class "Default")
      (node (ref "U11") (pin "77") (pinfunction "QO23_77") (pintype "passive+no_connect"))
    )
    (net (code "119") (name "unconnected-(U11-~{PDO}-Pad9)") (class "Default")
      (node (ref "U11") (pin "9") (pinfunction "~{PDO}_9") (pintype "passive+no_connect"))
    )
    (net (code "120") (name "unconnected-(U11-~{PD}-Pad2)") (class "Default")
      (node (ref "U11") (pin "2") (pinfunction "~{PD}_2") (pintype "passive+no_connect"))
    )
  )
)
